# revision0.net
KiCad netlist of a schematic drawn in EAGLE
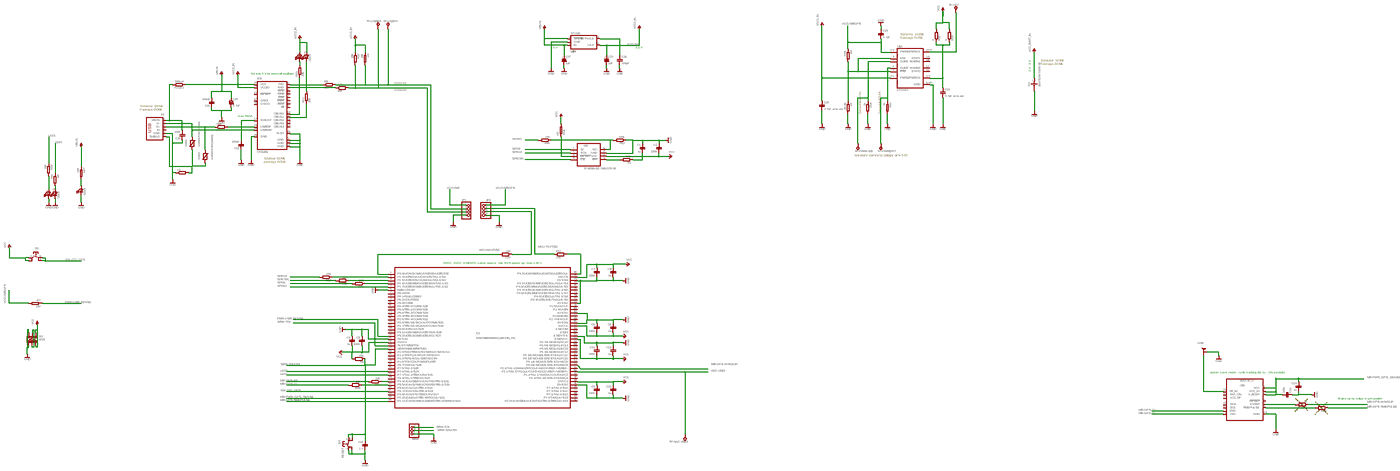
[diagram p0: schematic, sheet 1, overview]
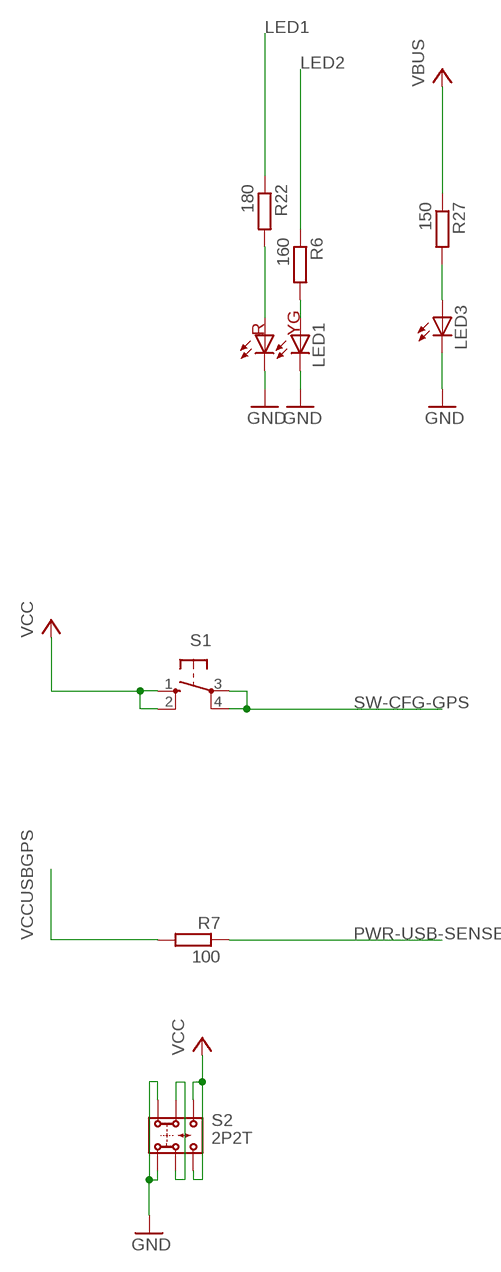
[diagram p1: schematic, sheet 1, part 1 of 4]
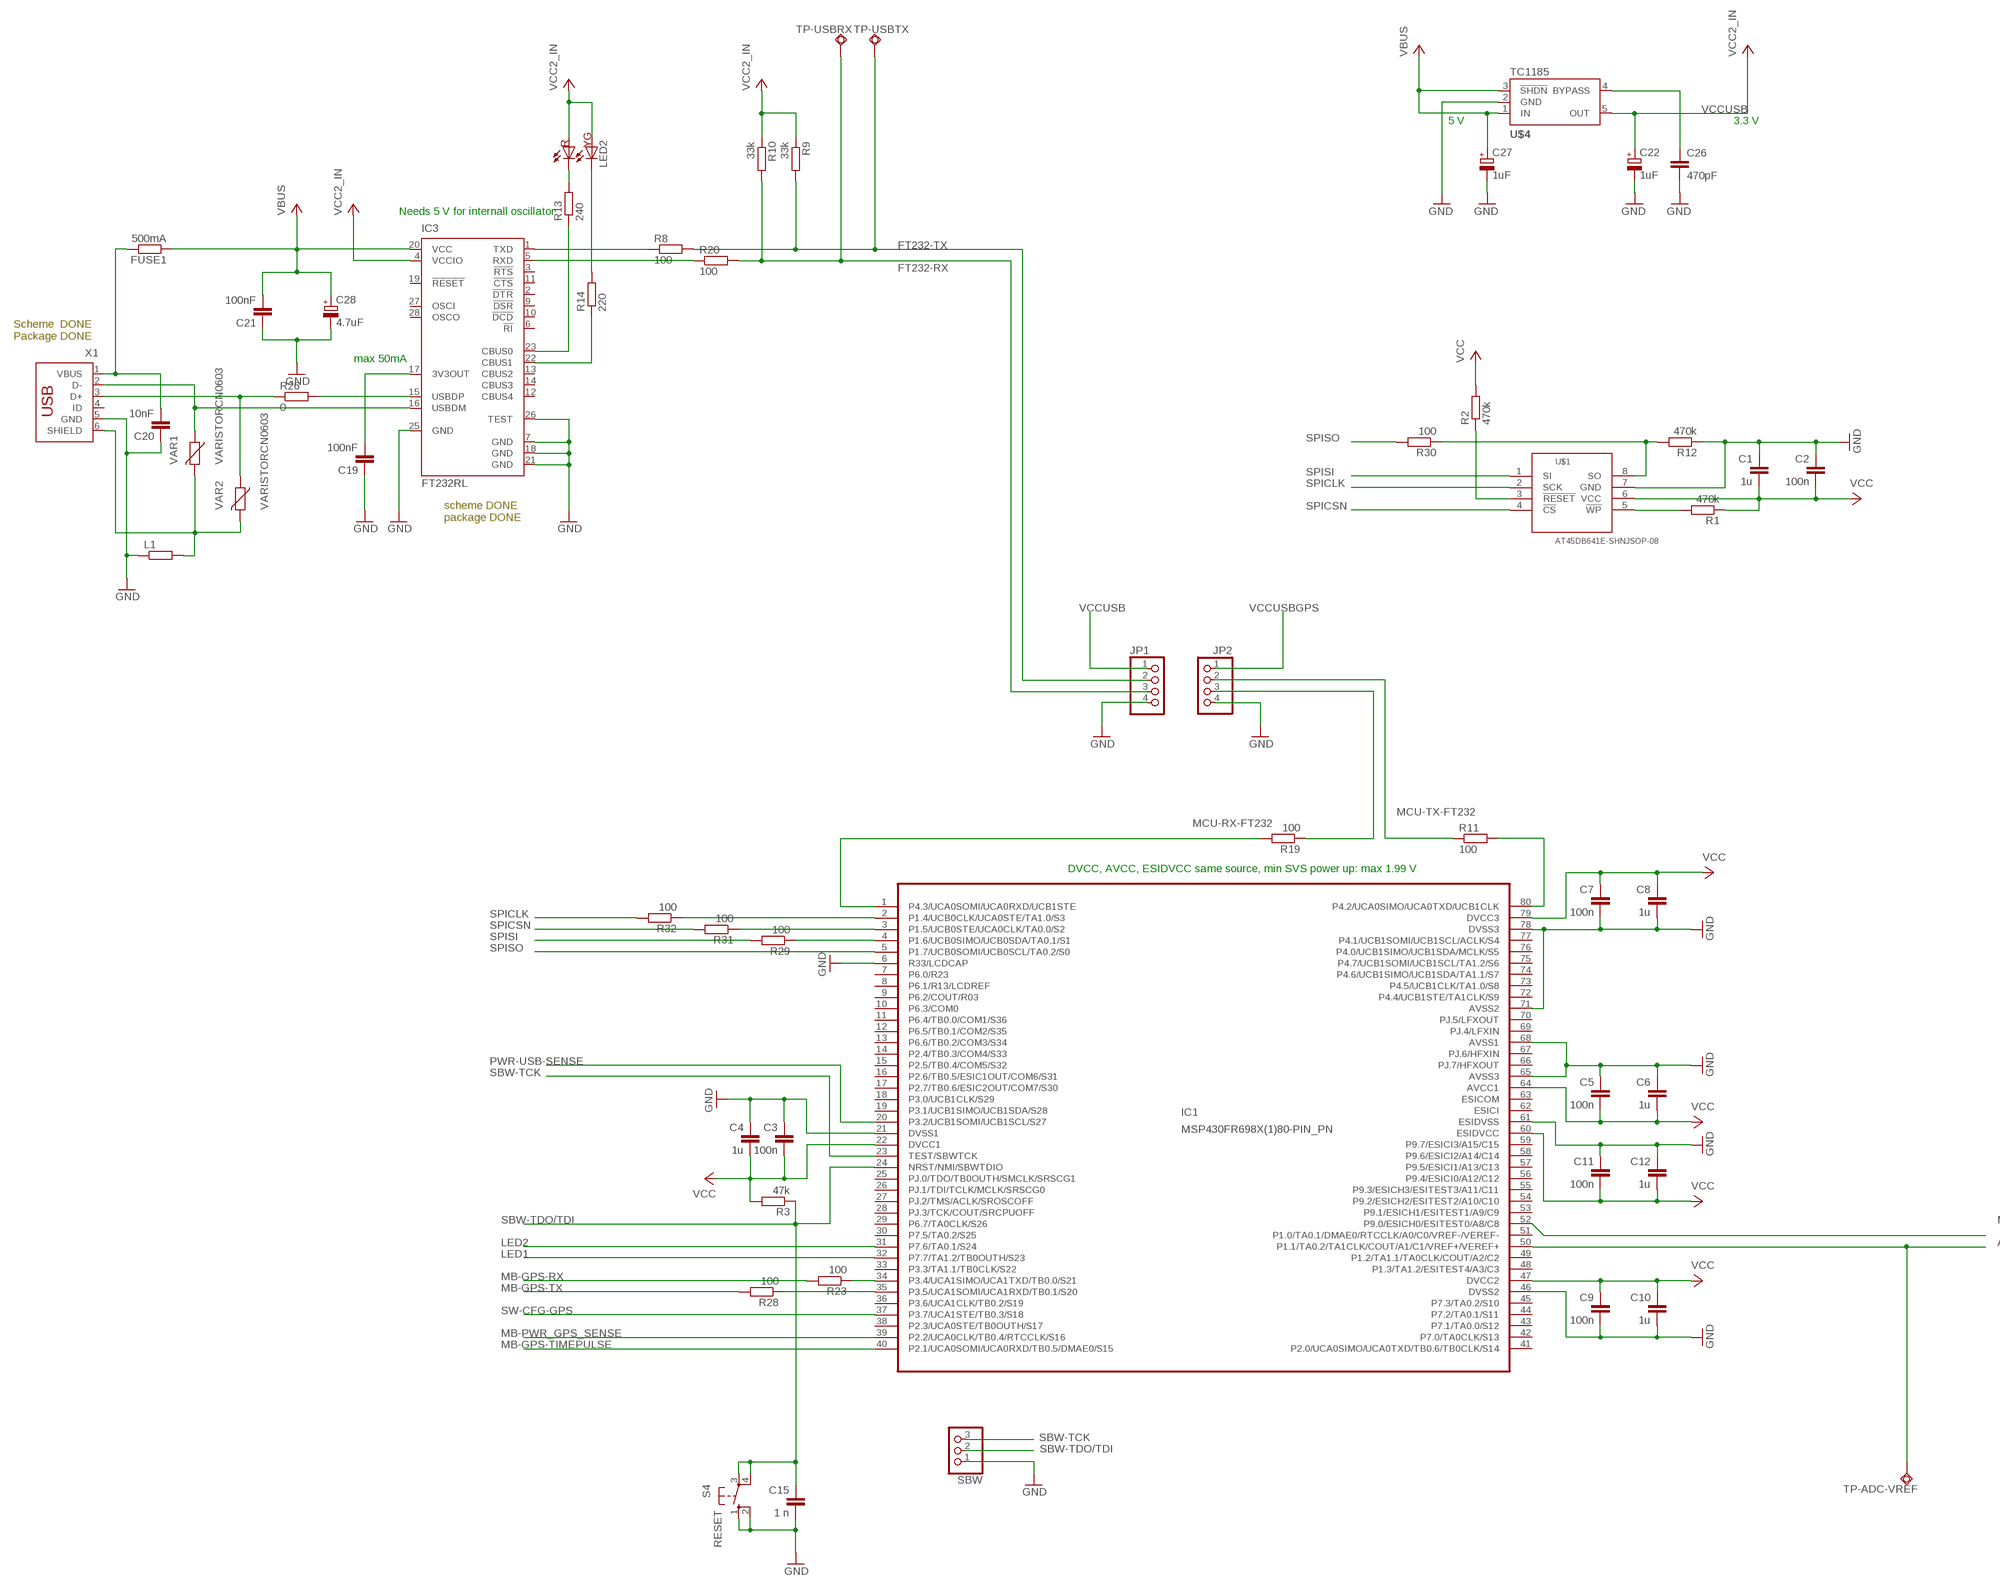
[diagram p2: schematic, sheet 1, part 2 of 4]
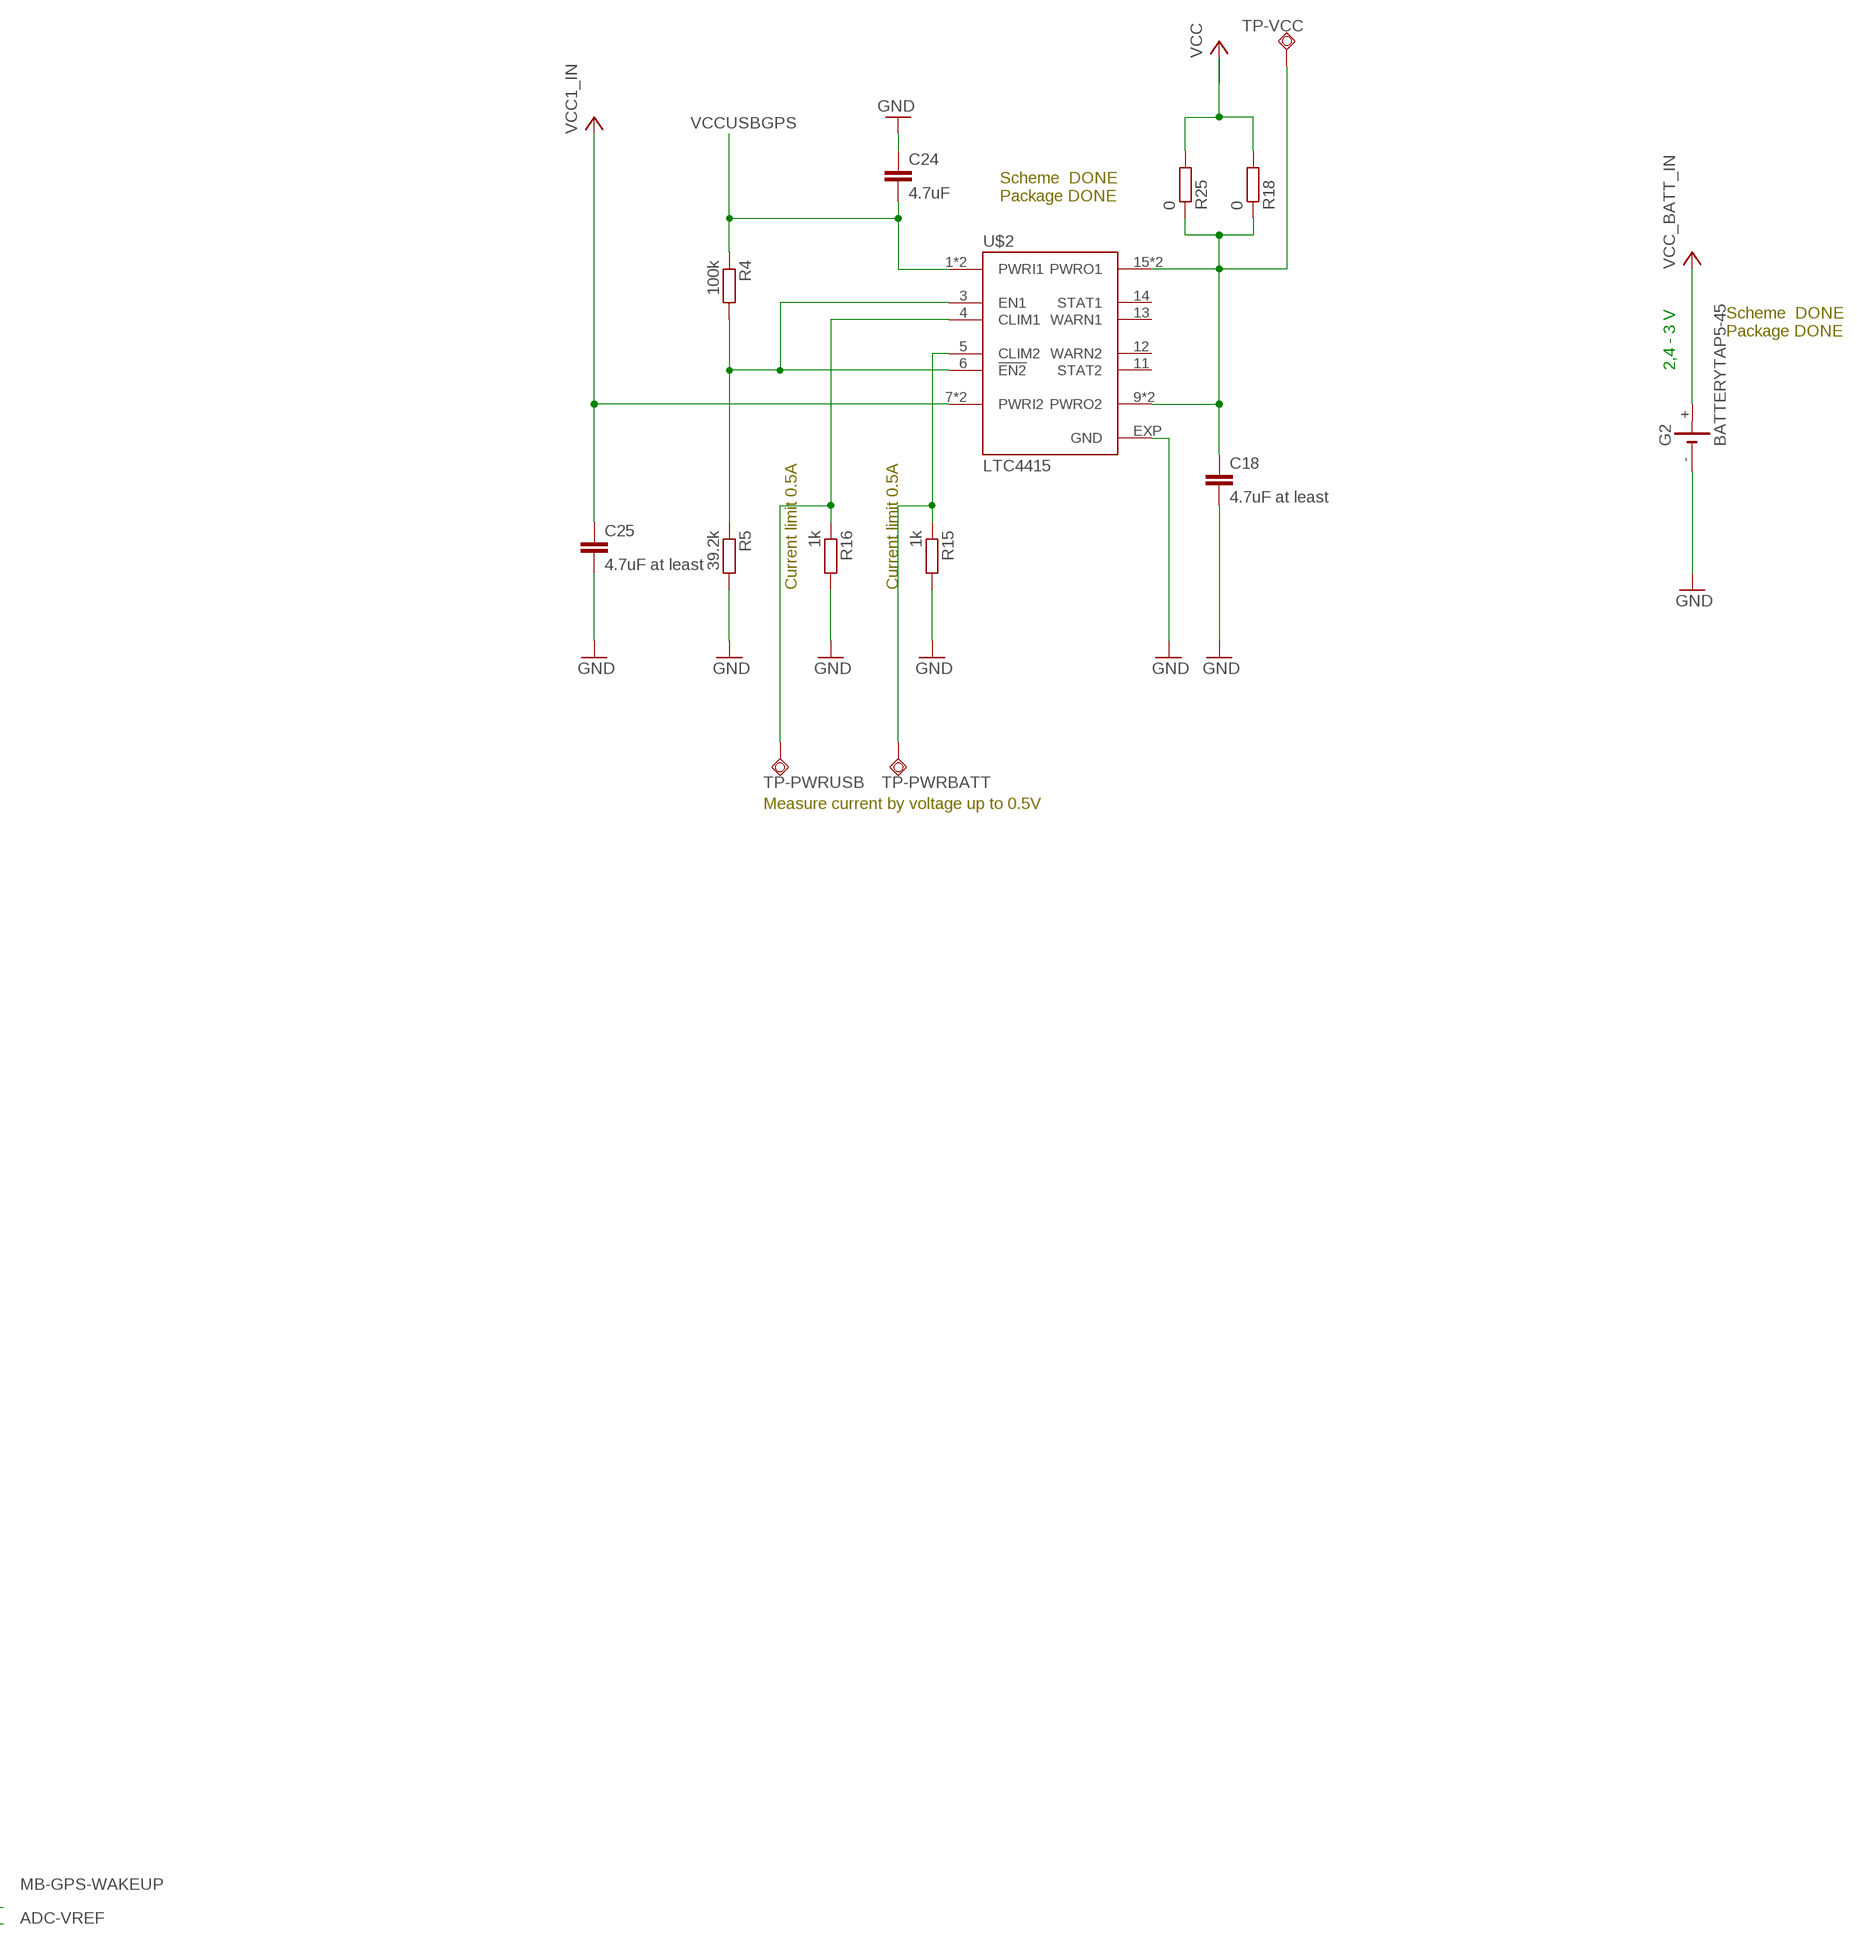
[diagram p3: schematic, sheet 1, part 3 of 4]
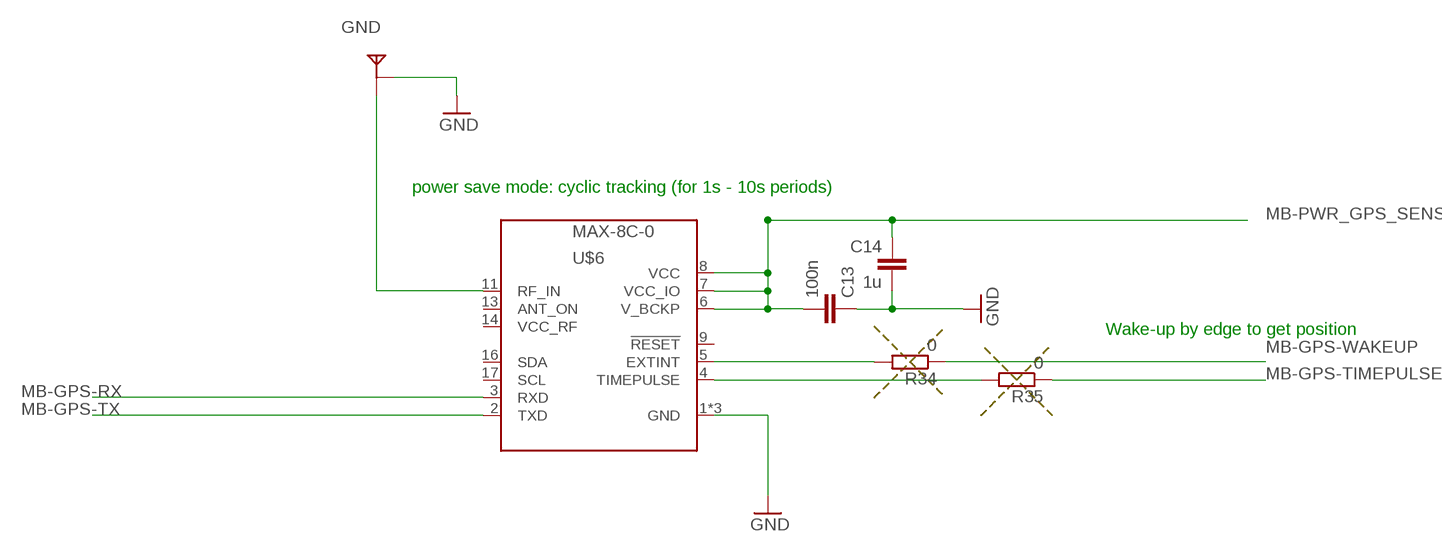
[diagram p4: schematic, sheet 1, part 4 of 4]

(export (version "E")
  (design (tool "Eeschema 10.0.6"))
  (components
    (comp (ref "C1")
      (value "1u")
      (footprint "eagle-import:C0603")
      (libsource (lib "eagle-import") (part "C-EUC0603"))
    )
    (comp (ref "C2")
      (value "100n")
      (footprint "eagle-import:C0603")
      (libsource (lib "eagle-import") (part "C-EUC0603"))
    )
    (comp (ref "C3")
      (value "100n")
      (footprint "eagle-import:C0603")
      (libsource (lib "eagle-import") (part "C-EUC0603"))
    )
    (comp (ref "C4")
      (value "1u")
      (footprint "eagle-import:C0603")
      (libsource (lib "eagle-import") (part "C-EUC0603"))
    )
    (comp (ref "C5")
      (value "100n")
      (footprint "eagle-import:C0603")
      (libsource (lib "eagle-import") (part "C-EUC0603"))
    )
    (comp (ref "C6")
      (value "1u")
      (footprint "eagle-import:C0603")
      (libsource (lib "eagle-import") (part "C-EUC0603"))
    )
    (comp (ref "C7")
      (value "100n")
      (footprint "eagle-import:C0603")
      (libsource (lib "eagle-import") (part "C-EUC0603"))
    )
    (comp (ref "C8")
      (value "1u")
      (footprint "eagle-import:C0603")
      (libsource (lib "eagle-import") (part "C-EUC0603"))
    )
    (comp (ref "C9")
      (value "100n")
      (footprint "eagle-import:C0603")
      (libsource (lib "eagle-import") (part "C-EUC0603"))
    )
    (comp (ref "C10")
      (value "1u")
      (footprint "eagle-import:C0603")
      (libsource (lib "eagle-import") (part "C-EUC0603"))
    )
    (comp (ref "C11")
      (value "100n")
      (footprint "eagle-import:C0603")
      (libsource (lib "eagle-import") (part "C-EUC0603"))
    )
    (comp (ref "C12")
      (value "1u")
      (footprint "eagle-import:C0603")
      (libsource (lib "eagle-import") (part "C-EUC0603"))
    )
    (comp (ref "C13")
      (value "100n")
      (footprint "eagle-import:C0603")
      (libsource (lib "eagle-import") (part "C-EUC0603"))
    )
    (comp (ref "C14")
      (value "1u")
      (footprint "eagle-import:C0603")
      (libsource (lib "eagle-import") (part "C-EUC0603"))
    )
    (comp (ref "C15")
      (value "1 n")
      (footprint "eagle-import:C0603")
      (libsource (lib "eagle-import") (part "C-EUC0603"))
    )
    (comp (ref "C18")
      (value "4.7uF at least")
      (footprint "eagle-import:C0805")
      (libsource (lib "eagle-import") (part "C-EUC0805"))
    )
    (comp (ref "C19")
      (value "100nF")
      (footprint "eagle-import:C0603")
      (libsource (lib "eagle-import") (part "C-EUC0603"))
    )
    (comp (ref "C20")
      (value "10nF")
      (footprint "eagle-import:C0603")
      (libsource (lib "eagle-import") (part "C-EUC0603"))
    )
    (comp (ref "C21")
      (value "100nF")
      (footprint "eagle-import:C0603")
      (libsource (lib "eagle-import") (part "C-EUC0603"))
    )
    (comp (ref "C22")
      (value "1uF")
      (footprint "eagle-import:A_3216-18W")
      (libsource (lib "eagle-import") (part "CPOL-EUA/3216-18W"))
    )
    (comp (ref "C24")
      (value "4.7uF")
      (footprint "eagle-import:C0805")
      (libsource (lib "eagle-import") (part "C-EUC0805"))
    )
    (comp (ref "C25")
      (value "4.7uF at least")
      (footprint "eagle-import:C0805")
      (libsource (lib "eagle-import") (part "C-EUC0805"))
    )
    (comp (ref "C26")
      (value "470pF")
      (footprint "eagle-import:C0603")
      (libsource (lib "eagle-import") (part "C-EUC0603"))
    )
    (comp (ref "C27")
      (value "1uF")
      (footprint "eagle-import:A_3216-18W")
      (libsource (lib "eagle-import") (part "CPOL-EUA/3216-18W"))
    )
    (comp (ref "C28")
      (value "4.7uF")
      (footprint "eagle-import:A_3216-18W")
      (libsource (lib "eagle-import") (part "CPOL-EUA/3216-18W"))
    )
    (comp (ref "FUSE1")
      (value "500mA")
      (footprint "eagle-import:R0805")
      (libsource (lib "eagle-import") (part "R-EU_R0805"))
    )
    (comp (ref "G2")
      (value "BATTERYTAP5-45")
      (footprint "eagle-import:TAP5-45")
      (libsource (lib "eagle-import") (part "BATTERYTAP5-45"))
    )
    (comp (ref "IC1")
      (value "MSP430FR698X(1)80-PIN_PN")
      (footprint "eagle-import:PN_S-PQFP-G80")
      (libsource (lib "eagle-import") (part "MSP430FR698X(1)80-PIN_PN"))
    )
    (comp (ref "IC3")
      (value "FT232RL")
      (footprint "eagle-import:SSOP28")
      (libsource (lib "eagle-import") (part "FT232RL"))
    )
    (comp (ref "JP1")
      (value "PINHD-1X4")
      (footprint "eagle-import:1X04")
      (libsource (lib "eagle-import") (part "PINHD-1X4"))
    )
    (comp (ref "JP2")
      (value "PINHD-1X4")
      (footprint "eagle-import:1X04")
      (libsource (lib "eagle-import") (part "PINHD-1X4"))
    )
    (comp (ref "L1")
      (value "R-EU_R0603")
      (footprint "eagle-import:R0603")
      (libsource (lib "eagle-import") (part "R-EU_R0603"))
    )
    (comp (ref "LED1")
      (value "BILEDBILED")
      (footprint "eagle-import:BILED")
      (libsource (lib "eagle-import") (part "BILEDBILED"))
    )
    (comp (ref "LED2")
      (value "BILEDBILED")
      (footprint "eagle-import:BILED")
      (libsource (lib "eagle-import") (part "BILEDBILED"))
    )
    (comp (ref "LED3")
      (value "LED_E")
      (footprint "eagle-import:LED_KINGBRIGHT0603")
      (libsource (lib "eagle-import") (part "LED_E"))
    )
    (comp (ref "R1")
      (value "470k")
      (footprint "eagle-import:R0603")
      (libsource (lib "eagle-import") (part "R-EU_R0603"))
    )
    (comp (ref "R2")
      (value "470k")
      (footprint "eagle-import:R0603")
      (libsource (lib "eagle-import") (part "R-EU_R0603"))
    )
    (comp (ref "R3")
      (value "47k")
      (footprint "eagle-import:R0603")
      (libsource (lib "eagle-import") (part "R-EU_R0603"))
    )
    (comp (ref "R4")
      (value "100k")
      (footprint "eagle-import:R0603")
      (libsource (lib "eagle-import") (part "R-EU_R0603"))
    )
    (comp (ref "R5")
      (value "39.2k")
      (footprint "eagle-import:R0603")
      (libsource (lib "eagle-import") (part "R-EU_R0603"))
    )
    (comp (ref "R6")
      (value "160")
      (footprint "eagle-import:R0603")
      (libsource (lib "eagle-import") (part "R-EU_R0603"))
    )
    (comp (ref "R7")
      (value "100")
      (footprint "eagle-import:R0603")
      (libsource (lib "eagle-import") (part "R-EU_R0603"))
    )
    (comp (ref "R8")
      (value "100")
      (footprint "eagle-import:R0603")
      (libsource (lib "eagle-import") (part "R-EU_R0603"))
    )
    (comp (ref "R9")
      (value "33k")
      (footprint "eagle-import:R0603")
      (libsource (lib "eagle-import") (part "R-EU_R0603"))
    )
    (comp (ref "R10")
      (value "33k")
      (footprint "eagle-import:R0603")
      (libsource (lib "eagle-import") (part "R-EU_R0603"))
    )
    (comp (ref "R11")
      (value "100")
      (footprint "eagle-import:R0603")
      (libsource (lib "eagle-import") (part "R-EU_R0603"))
    )
    (comp (ref "R12")
      (value "470k")
      (footprint "eagle-import:R0603")
      (libsource (lib "eagle-import") (part "R-EU_R0603"))
    )
    (comp (ref "R13")
      (value "240")
      (footprint "eagle-import:R0603")
      (libsource (lib "eagle-import") (part "R-EU_R0603"))
    )
    (comp (ref "R14")
      (value "220")
      (footprint "eagle-import:R0603")
      (libsource (lib "eagle-import") (part "R-EU_R0603"))
    )
    (comp (ref "R15")
      (value "1k")
      (footprint "eagle-import:R0603")
      (libsource (lib "eagle-import") (part "R-EU_R0603"))
    )
    (comp (ref "R16")
      (value "1k")
      (footprint "eagle-import:R0603")
      (libsource (lib "eagle-import") (part "R-EU_R0603"))
    )
    (comp (ref "R18")
      (value "0")
      (footprint "eagle-import:R0603")
      (libsource (lib "eagle-import") (part "R-EU_R0603"))
    )
    (comp (ref "R19")
      (value "100")
      (footprint "eagle-import:R0603")
      (libsource (lib "eagle-import") (part "R-EU_R0603"))
    )
    (comp (ref "R20")
      (value "100")
      (footprint "eagle-import:R0603")
      (libsource (lib "eagle-import") (part "R-EU_R0603"))
    )
    (comp (ref "R22")
      (value "180")
      (footprint "eagle-import:R0603")
      (libsource (lib "eagle-import") (part "R-EU_R0603"))
    )
    (comp (ref "R23")
      (value "100")
      (footprint "eagle-import:R0603")
      (libsource (lib "eagle-import") (part "R-EU_R0603"))
    )
    (comp (ref "R25")
      (value "0")
      (footprint "eagle-import:R0603")
      (libsource (lib "eagle-import") (part "R-EU_R0603"))
    )
    (comp (ref "R26")
      (value "0")
      (footprint "eagle-import:R0603")
      (libsource (lib "eagle-import") (part "R-EU_R0603"))
    )
    (comp (ref "R27")
      (value "150")
      (footprint "eagle-import:R0603")
      (libsource (lib "eagle-import") (part "R-EU_R0603"))
    )
    (comp (ref "R28")
      (value "100")
      (footprint "eagle-import:R0603")
      (libsource (lib "eagle-import") (part "R-EU_R0603"))
    )
    (comp (ref "R29")
      (value "100")
      (footprint "eagle-import:R0603")
      (libsource (lib "eagle-import") (part "R-EU_R0603"))
    )
    (comp (ref "R30")
      (value "100")
      (footprint "eagle-import:R0603")
      (libsource (lib "eagle-import") (part "R-EU_R0603"))
    )
    (comp (ref "R31")
      (value "100")
      (footprint "eagle-import:R0603")
      (libsource (lib "eagle-import") (part "R-EU_R0603"))
    )
    (comp (ref "R32")
      (value "100")
      (footprint "eagle-import:R0603")
      (libsource (lib "eagle-import") (part "R-EU_R0603"))
    )
    (comp (ref "R34")
      (value "0")
      (footprint "eagle-import:R0603")
      (libsource (lib "eagle-import") (part "R-EU_R0603"))
    )
    (comp (ref "R35")
      (value "0")
      (footprint "eagle-import:R0603")
      (libsource (lib "eagle-import") (part "R-EU_R0603"))
    )
    (comp (ref "S1")
      (value "SWITCH-10-XX")
      (footprint "eagle-import:B3F-10XX")
      (fields (field (name "MPN") "B3F-1000"))
      (libsource (lib "eagle-import") (part "SWITCH-10-XX"))
    )
    (comp (ref "S2")
      (value "2P2T")
      (footprint "eagle-import:2P2T")
      (libsource (lib "eagle-import") (part "2P2T"))
    )
    (comp (ref "S4")
      (value "RESET")
      (footprint "eagle-import:B3F-10XX")
      (fields (field (name "MPN") "B3F-1000"))
      (libsource (lib "eagle-import") (part "SWITCH-10-XX"))
    )
    (comp (ref "SBW")
      (value "PINHD-1X3")
      (footprint "eagle-import:1X03")
      (libsource (lib "eagle-import") (part "PINHD-1X3"))
    )
    (comp (ref "TP-ADC-VREF")
      (value "TPSQTP10R")
      (footprint "eagle-import:TP10R")
      (libsource (lib "eagle-import") (part "TPSQTP10R"))
    )
    (comp (ref "TP-PWRBATT")
      (value "TPSQTP10R")
      (footprint "eagle-import:TP10R")
      (libsource (lib "eagle-import") (part "TPSQTP10R"))
    )
    (comp (ref "TP-PWRUSB")
      (value "TPSQTP10R")
      (footprint "eagle-import:TP10R")
      (libsource (lib "eagle-import") (part "TPSQTP10R"))
    )
    (comp (ref "TP-USBRX")
      (value "TPSQPAD1-13")
      (footprint "eagle-import:P1-13")
      (libsource (lib "eagle-import") (part "TPSQPAD1-13"))
    )
    (comp (ref "TP-USBTX")
      (value "TPSQPAD1-13")
      (footprint "eagle-import:P1-13")
      (libsource (lib "eagle-import") (part "TPSQPAD1-13"))
    )
    (comp (ref "TP-VCC")
      (value "TPSQPAD1-13")
      (footprint "eagle-import:P1-13")
      (libsource (lib "eagle-import") (part "TPSQPAD1-13"))
    )
    (comp (ref "U$1")
      (value "AT45DB641E-SHNJSOP-08")
      (footprint "eagle-import:JSOP-08")
      (libsource (lib "eagle-import") (part "AT45DB641E-SHNJSOP-08"))
    )
    (comp (ref "U$2")
      (value "LTC4415")
      (footprint "eagle-import:MSOP16")
      (libsource (lib "eagle-import") (part "LTC4415"))
    )
    (comp (ref "U$4")
      (value "TC1185")
      (footprint "eagle-import:SOT23-5")
      (libsource (lib "eagle-import") (part "TC1185"))
    )
    (comp (ref "U$5")
      (value "MWSL1251")
      (footprint "eagle-import:MWSL1251")
      (libsource (lib "eagle-import") (part "MWSL1251"))
    )
    (comp (ref "U$6")
      (value "MAX-8C-0")
      (footprint "eagle-import:MAX-8")
      (libsource (lib "eagle-import") (part "MAX-8C-0"))
    )
    (comp (ref "VAR1")
      (value "VARISTORCN0603")
      (footprint "eagle-import:CT_CN0603")
      (libsource (lib "eagle-import") (part "VARISTORCN0603"))
    )
    (comp (ref "VAR2")
      (value "VARISTORCN0603")
      (footprint "eagle-import:CT_CN0603")
      (libsource (lib "eagle-import") (part "VARISTORCN0603"))
    )
    (comp (ref "X1")
      (value "USB-787616")
      (footprint "eagle-import:USB")
      (libsource (lib "eagle-import") (part "USB-787616"))
    )
  )
  (nets
    (net (code "1") (name "/ADC-VREF") (class "Default")
      (node (ref "IC1") (pin "50") (pinfunction "P1.1/TA0.2/TA1CLK/COUT/A1/C1/VREF+/VEREF+_50") (pintype "bidirectional"))
      (node (ref "TP-ADC-VREF") (pin "TP") (pinfunction "TP_TP") (pintype "input"))
    )
    (net (code "2") (name "/FT232-RX") (class "Default")
      (node (ref "JP1") (pin "3") (pinfunction "3_3") (pintype "passive"))
      (node (ref "R10") (pin "2") (pinfunction "2_2") (pintype "passive"))
      (node (ref "R20") (pin "2") (pinfunction "2_2") (pintype "passive"))
      (node (ref "TP-USBRX") (pin "TP") (pinfunction "TP_TP") (pintype "input"))
    )
    (net (code "3") (name "/FT232-TX") (class "Default")
      (node (ref "JP1") (pin "2") (pinfunction "2_2") (pintype "passive"))
      (node (ref "R8") (pin "2") (pinfunction "2_2") (pintype "passive"))
      (node (ref "R9") (pin "2") (pinfunction "2_2") (pintype "passive"))
      (node (ref "TP-USBTX") (pin "TP") (pinfunction "TP_TP") (pintype "input"))
    )
    (net (code "4") (name "/LED1") (class "Default")
      (node (ref "IC1") (pin "32") (pinfunction "P7.7/TA1.2/TB0OUTH/S23_32") (pintype "bidirectional"))
      (node (ref "R22") (pin "1") (pinfunction "1_1") (pintype "passive"))
    )
    (net (code "5") (name "/LED2") (class "Default")
      (node (ref "IC1") (pin "31") (pinfunction "P7.6/TA0.1/S24_31") (pintype "bidirectional"))
      (node (ref "R6") (pin "1") (pinfunction "1_1") (pintype "passive"))
    )
    (net (code "6") (name "/MB-GPS-RX") (class "Default")
      (node (ref "R23") (pin "2") (pinfunction "2_2") (pintype "passive"))
      (node (ref "U$6") (pin "3") (pinfunction "RXD_3") (pintype "input"))
    )
    (net (code "7") (name "/MB-GPS-TIMEPULSE") (class "Default")
      (node (ref "IC1") (pin "40") (pinfunction "P2.1/UCA0SOMI/UCA0RXD/TB0.5/DMAE0/S15_40") (pintype "bidirectional"))
      (node (ref "R35") (pin "1") (pinfunction "1_1") (pintype "passive"))
    )
    (net (code "8") (name "/MB-GPS-TX") (class "Default")
      (node (ref "R28") (pin "2") (pinfunction "2_2") (pintype "passive"))
      (node (ref "U$6") (pin "2") (pinfunction "TXD_2") (pintype "output"))
    )
    (net (code "9") (name "/MB-GPS-WAKEUP") (class "Default")
      (node (ref "IC1") (pin "52") (pinfunction "P9.0/ESICH0/ESITEST0/A8/C8_52") (pintype "bidirectional"))
      (node (ref "R34") (pin "1") (pinfunction "1_1") (pintype "passive"))
    )
    (net (code "10") (name "/MB-PWR_GPS_SENSE") (class "Default")
      (node (ref "C13") (pin "2") (pinfunction "2_2") (pintype "passive"))
      (node (ref "C14") (pin "1") (pinfunction "1_1") (pintype "passive"))
      (node (ref "IC1") (pin "39") (pinfunction "P2.2/UCA0CLK/TB0.4/RTCCLK/S16_39") (pintype "bidirectional"))
      (node (ref "S2") (pin "2.1") (pinfunction "2.1_2.1") (pintype "passive"))
      (node (ref "S2") (pin "2.2") (pinfunction "2.2_2.2") (pintype "passive"))
      (node (ref "U$6") (pin "6") (pinfunction "V_BCKP_6") (pintype "power_in"))
      (node (ref "U$6") (pin "7") (pinfunction "VCC_IO_7") (pintype "power_in"))
      (node (ref "U$6") (pin "8") (pinfunction "VCC_8") (pintype "power_in"))
    )
    (net (code "11") (name "/MCU-RX-FT232") (class "Default")
      (node (ref "IC1") (pin "1") (pinfunction "P4.3/UCA0SOMI/UCA0RXD/UCB1STE_1") (pintype "bidirectional"))
      (node (ref "R19") (pin "2") (pinfunction "2_2") (pintype "passive"))
    )
    (net (code "12") (name "/MCU-TX-FT232") (class "Default")
      (node (ref "JP2") (pin "2") (pinfunction "2_2") (pintype "passive"))
      (node (ref "R11") (pin "1") (pinfunction "1_1") (pintype "passive"))
    )
    (net (code "13") (name "/PWR-USB-SENSE") (class "Default")
      (node (ref "IC1") (pin "20") (pinfunction "P3.2/UCB1SOMI/UCB1SCL/S27_20") (pintype "bidirectional"))
      (node (ref "R7") (pin "1") (pinfunction "1_1") (pintype "passive"))
    )
    (net (code "14") (name "/SBW-TCK") (class "Default")
      (node (ref "IC1") (pin "23") (pinfunction "TEST/SBWTCK_23") (pintype "output"))
      (node (ref "SBW") (pin "3") (pinfunction "3_3") (pintype "passive"))
    )
    (net (code "15") (name "/SBW-TDO{slash}TDI") (class "Default")
      (node (ref "C15") (pin "1") (pinfunction "1_1") (pintype "passive"))
      (node (ref "IC1") (pin "24") (pinfunction "NRST/NMI/SBWTDIO_24") (pintype "bidirectional"))
      (node (ref "R3") (pin "1") (pinfunction "1_1") (pintype "passive"))
      (node (ref "S4") (pin "3") (pinfunction "P_3") (pintype "passive"))
      (node (ref "S4") (pin "4") (pinfunction "P1_4") (pintype "passive"))
      (node (ref "SBW") (pin "2") (pinfunction "2_2") (pintype "passive"))
    )
    (net (code "16") (name "/SPICLK") (class "Default")
      (node (ref "R32") (pin "2") (pinfunction "2_2") (pintype "passive"))
      (node (ref "U$1") (pin "2") (pinfunction "SCK_2") (pintype "input"))
    )
    (net (code "17") (name "/SPICSN") (class "Default")
      (node (ref "R31") (pin "2") (pinfunction "2_2") (pintype "passive"))
      (node (ref "U$1") (pin "4") (pinfunction "~{CS}_4") (pintype "input"))
    )
    (net (code "18") (name "/SPISI") (class "Default")
      (node (ref "R29") (pin "2") (pinfunction "2_2") (pintype "passive"))
      (node (ref "U$1") (pin "1") (pinfunction "SI_1") (pintype "input"))
    )
    (net (code "19") (name "/SPISO") (class "Default")
      (node (ref "IC1") (pin "5") (pinfunction "P1.7/UCB0SOMI/UCB0SCL/TA0.2/S0_5") (pintype "bidirectional"))
      (node (ref "R30") (pin "2") (pinfunction "2_2") (pintype "passive"))
    )
    (net (code "20") (name "/SW-CFG-GPS") (class "Default")
      (node (ref "IC1") (pin "37") (pinfunction "P3.7/UCA1STE/TB0.3/S18_37") (pintype "bidirectional"))
      (node (ref "S1") (pin "3") (pinfunction "P_3") (pintype "passive"))
      (node (ref "S1") (pin "4") (pinfunction "P1_4") (pintype "passive"))
    )
    (net (code "21") (name "/VCCUSBGPS") (class "Default")
      (node (ref "C24") (pin "2") (pinfunction "2_2") (pintype "passive"))
      (node (ref "JP2") (pin "1") (pinfunction "1_1") (pintype "passive"))
      (node (ref "R4") (pin "1") (pinfunction "1_1") (pintype "passive"))
      (node (ref "R7") (pin "2") (pinfunction "2_2") (pintype "passive"))
      (node (ref "U$2") (pin "1") (pinfunction "PWRI1_1") (pintype "power_in"))
      (node (ref "U$2") (pin "2") (pinfunction "PWRI1_2") (pintype "power_in"))
    )
    (net (code "22") (name "GND") (class "Default")
      (node (ref "C1") (pin "1") (pinfunction "1_1") (pintype "passive"))
      (node (ref "C10") (pin "2") (pinfunction "2_2") (pintype "passive"))
      (node (ref "C11") (pin "1") (pinfunction "1_1") (pintype "passive"))
      (node (ref "C12") (pin "1") (pinfunction "1_1") (pintype "passive"))
      (node (ref "C13") (pin "1") (pinfunction "1_1") (pintype "passive"))
      (node (ref "C14") (pin "2") (pinfunction "2_2") (pintype "passive"))
      (node (ref "C15") (pin "2") (pinfunction "2_2") (pintype "passive"))
      (node (ref "C18") (pin "2") (pinfunction "2_2") (pintype "passive"))
      (node (ref "C19") (pin "1") (pinfunction "1_1") (pintype "passive"))
      (node (ref "C2") (pin "1") (pinfunction "1_1") (pintype "passive"))
      (node (ref "C20") (pin "1") (pinfunction "1_1") (pintype "passive"))
      (node (ref "C21") (pin "1") (pinfunction "1_1") (pintype "passive"))
      (node (ref "C22") (pin "-") (pinfunction "-_-") (pintype "passive"))
      (node (ref "C24") (pin "1") (pinfunction "1_1") (pintype "passive"))
      (node (ref "C25") (pin "2") (pinfunction "2_2") (pintype "passive"))
      (node (ref "C26") (pin "2") (pinfunction "2_2") (pintype "passive"))
      (node (ref "C27") (pin "-") (pinfunction "-_-") (pintype "passive"))
      (node (ref "C28") (pin "-") (pinfunction "-_-") (pintype "passive"))
      (node (ref "C3") (pin "1") (pinfunction "1_1") (pintype "passive"))
      (node (ref "C4") (pin "1") (pinfunction "1_1") (pintype "passive"))
      (node (ref "C5") (pin "1") (pinfunction "1_1") (pintype "passive"))
      (node (ref "C6") (pin "1") (pinfunction "1_1") (pintype "passive"))
      (node (ref "C7") (pin "2") (pinfunction "2_2") (pintype "passive"))
      (node (ref "C8") (pin "2") (pinfunction "2_2") (pintype "passive"))
      (node (ref "C9") (pin "2") (pinfunction "2_2") (pintype "passive"))
      (node (ref "G2") (pin "-") (pinfunction "-_-") (pintype "passive"))
      (node (ref "IC1") (pin "21") (pinfunction "DVSS1_21") (pintype "power_in"))
      (node (ref "IC1") (pin "46") (pinfunction "DVSS2_46") (pintype "power_in"))
      (node (ref "IC1") (pin "6") (pinfunction "R33/LCDCAP_6") (pintype "bidirectional"))
      (node (ref "IC1") (pin "61") (pinfunction "ESIDVSS_61") (pintype "power_in"))
      (node (ref "IC1") (pin "65") (pinfunction "AVSS3_65") (pintype "power_in"))
      (node (ref "IC1") (pin "68") (pinfunction "AVSS1_68") (pintype "power_in"))
      (node (ref "IC1") (pin "71") (pinfunction "AVSS2_71") (pintype "power_in"))
      (node (ref "IC1") (pin "78") (pinfunction "DVSS3_78") (pintype "power_in"))
      (node (ref "IC3") (pin "18") (pinfunction "GND_18") (pintype "power_in"))
      (node (ref "IC3") (pin "21") (pinfunction "GND_21") (pintype "power_in"))
      (node (ref "IC3") (pin "25") (pinfunction "GND_25") (pintype "power_in"))
      (node (ref "IC3") (pin "26") (pinfunction "TEST_26") (pintype "input"))
      (node (ref "IC3") (pin "7") (pinfunction "GND_7") (pintype "power_in"))
      (node (ref "JP1") (pin "4") (pinfunction "4_4") (pintype "passive"))
      (node (ref "JP2") (pin "4") (pinfunction "4_4") (pintype "passive"))
      (node (ref "L1") (pin "1") (pinfunction "1_1") (pintype "passive"))
      (node (ref "LED1") (pin "1") (pinfunction "1_1") (pintype "passive"))
      (node (ref "LED1") (pin "3") (pinfunction "3_3") (pintype "passive"))
      (node (ref "LED3") (pin "C") (pinfunction "C_C") (pintype "passive"))
      (node (ref "R12") (pin "1") (pinfunction "1_1") (pintype "passive"))
      (node (ref "R15") (pin "2") (pinfunction "2_2") (pintype "passive"))
      (node (ref "R16") (pin "2") (pinfunction "2_2") (pintype "passive"))
      (node (ref "R5") (pin "2") (pinfunction "2_2") (pintype "passive"))
      (node (ref "S2") (pin "1.1") (pinfunction "1.1_1.1") (pintype "passive"))
      (node (ref "S2") (pin "1.2") (pinfunction "1.2_1.2") (pintype "passive"))
      (node (ref "S4") (pin "1") (pinfunction "S_1") (pintype "passive"))
      (node (ref "S4") (pin "2") (pinfunction "S1_2") (pintype "passive"))
      (node (ref "SBW") (pin "1") (pinfunction "1_1") (pintype "passive"))
      (node (ref "U$1") (pin "7") (pinfunction "GND_7") (pintype "power_in"))
      (node (ref "U$2") (pin "EXP") (pinfunction "GND_EXP") (pintype "power_in"))
      (node (ref "U$4") (pin "2") (pinfunction "GND_2") (pintype "power_in"))
      (node (ref "U$5") (pin "P$1") (pinfunction "GND_P$1") (pintype "power_in"))
      (node (ref "U$5") (pin "P$3") (pinfunction "GND_P$3") (pintype "power_in"))
      (node (ref "U$6") (pin "1") (pinfunction "GND_1") (pintype "power_in"))
      (node (ref "U$6") (pin "10") (pinfunction "GND_10") (pintype "power_in"))
      (node (ref "U$6") (pin "12") (pinfunction "GND_12") (pintype "power_in"))
      (node (ref "X1") (pin "5") (pinfunction "GND_5") (pintype "passive"))
    )
    (net (code "23") (name "Net-(C18-Pad1)") (class "Default")
      (node (ref "C18") (pin "1") (pinfunction "1_1") (pintype "passive"))
      (node (ref "R18") (pin "1") (pinfunction "1_1") (pintype "passive"))
      (node (ref "R25") (pin "1") (pinfunction "1_1") (pintype "passive"))
      (node (ref "TP-VCC") (pin "TP") (pinfunction "TP_TP") (pintype "input"))
      (node (ref "U$2") (pin "10") (pinfunction "PWRO2_10") (pintype "power_in"))
      (node (ref "U$2") (pin "15") (pinfunction "PWRO1_15") (pintype "power_in"))
      (node (ref "U$2") (pin "16") (pinfunction "PWRO1_16") (pintype "power_in"))
      (node (ref "U$2") (pin "9") (pinfunction "PWRO2_9") (pintype "power_in"))
    )
    (net (code "24") (name "Net-(IC1-P1.4{slash}UCB0CLK{slash}UCA0STE{slash}TA1.0{slash}S3)") (class "Default")
      (node (ref "IC1") (pin "2") (pinfunction "P1.4/UCB0CLK/UCA0STE/TA1.0/S3_2") (pintype "bidirectional"))
      (node (ref "R32") (pin "1") (pinfunction "1_1") (pintype "passive"))
    )
    (net (code "25") (name "Net-(IC1-P1.5{slash}UCB0STE{slash}UCA0CLK{slash}TA0.0{slash}S2)") (class "Default")
      (node (ref "IC1") (pin "3") (pinfunction "P1.5/UCB0STE/UCA0CLK/TA0.0/S2_3") (pintype "bidirectional"))
      (node (ref "R31") (pin "1") (pinfunction "1_1") (pintype "passive"))
    )
    (net (code "26") (name "Net-(IC1-P1.6{slash}UCB0SIMO{slash}UCB0SDA{slash}TA0.1{slash}S1)") (class "Default")
      (node (ref "IC1") (pin "4") (pinfunction "P1.6/UCB0SIMO/UCB0SDA/TA0.1/S1_4") (pintype "bidirectional"))
      (node (ref "R29") (pin "1") (pinfunction "1_1") (pintype "passive"))
    )
    (net (code "27") (name "Net-(IC1-P3.4{slash}UCA1SIMO{slash}UCA1TXD{slash}TB0.0{slash}S21)") (class "Default")
      (node (ref "IC1") (pin "34") (pinfunction "P3.4/UCA1SIMO/UCA1TXD/TB0.0/S21_34") (pintype "bidirectional"))
      (node (ref "R23") (pin "1") (pinfunction "1_1") (pintype "passive"))
    )
    (net (code "28") (name "Net-(IC1-P3.5{slash}UCA1SOMI{slash}UCA1RXD{slash}TB0.1{slash}S20)") (class "Default")
      (node (ref "IC1") (pin "35") (pinfunction "P3.5/UCA1SOMI/UCA1RXD/TB0.1/S20_35") (pintype "bidirectional"))
      (node (ref "R28") (pin "1") (pinfunction "1_1") (pintype "passive"))
    )
    (net (code "29") (name "Net-(IC1-P4.2{slash}UCA0SIMO{slash}UCA0TXD{slash}UCB1CLK)") (class "Default")
      (node (ref "IC1") (pin "80") (pinfunction "P4.2/UCA0SIMO/UCA0TXD/UCB1CLK_80") (pintype "bidirectional"))
      (node (ref "R11") (pin "2") (pinfunction "2_2") (pintype "passive"))
    )
    (net (code "30") (name "Net-(IC3-3V3OUT)") (class "Default")
      (node (ref "C19") (pin "2") (pinfunction "2_2") (pintype "passive"))
      (node (ref "IC3") (pin "17") (pinfunction "3V3OUT_17") (pintype "output"))
    )
    (net (code "31") (name "Net-(IC3-CBUS0)") (class "Default")
      (node (ref "IC3") (pin "23") (pinfunction "CBUS0_23") (pintype "bidirectional"))
      (node (ref "R13") (pin "1") (pinfunction "1_1") (pintype "passive"))
    )
    (net (code "32") (name "Net-(IC3-CBUS1)") (class "Default")
      (node (ref "IC3") (pin "22") (pinfunction "CBUS1_22") (pintype "bidirectional"))
      (node (ref "R14") (pin "1") (pinfunction "1_1") (pintype "passive"))
    )
    (net (code "33") (name "Net-(IC3-RXD)") (class "Default")
      (node (ref "IC3") (pin "5") (pinfunction "RXD_5") (pintype "input"))
      (node (ref "R20") (pin "1") (pinfunction "1_1") (pintype "passive"))
    )
    (net (code "34") (name "Net-(IC3-TXD)") (class "Default")
      (node (ref "IC3") (pin "1") (pinfunction "TXD_1") (pintype "output"))
      (node (ref "R8") (pin "1") (pinfunction "1_1") (pintype "passive"))
    )
    (net (code "35") (name "Net-(IC3-USBDM)") (class "Default")
      (node (ref "IC3") (pin "16") (pinfunction "USBDM_16") (pintype "bidirectional"))
      (node (ref "VAR1") (pin "1") (pinfunction "1_1") (pintype "passive"))
      (node (ref "X1") (pin "2") (pinfunction "D-_2") (pintype "passive"))
    )
    (net (code "36") (name "Net-(IC3-USBDP)") (class "Default")
      (node (ref "IC3") (pin "15") (pinfunction "USBDP_15") (pintype "bidirectional"))
      (node (ref "R26") (pin "2") (pinfunction "2_2") (pintype "passive"))
    )
    (net (code "37") (name "Net-(JP2-Pad3)") (class "Default")
      (node (ref "JP2") (pin "3") (pinfunction "3_3") (pintype "passive"))
      (node (ref "R19") (pin "1") (pinfunction "1_1") (pintype "passive"))
    )
    (net (code "38") (name "Net-(LED1-Pad2)") (class "Default")
      (node (ref "LED1") (pin "2") (pinfunction "2_2") (pintype "passive"))
      (node (ref "R22") (pin "2") (pinfunction "2_2") (pintype "passive"))
    )
    (net (code "39") (name "Net-(LED1-Pad4)") (class "Default")
      (node (ref "LED1") (pin "4") (pinfunction "4_4") (pintype "passive"))
      (node (ref "R6") (pin "2") (pinfunction "2_2") (pintype "passive"))
    )
    (net (code "40") (name "Net-(LED2-Pad1)") (class "Default")
      (node (ref "LED2") (pin "1") (pinfunction "1_1") (pintype "passive"))
      (node (ref "R13") (pin "2") (pinfunction "2_2") (pintype "passive"))
    )
    (net (code "41") (name "Net-(LED2-Pad3)") (class "Default")
      (node (ref "LED2") (pin "3") (pinfunction "3_3") (pintype "passive"))
      (node (ref "R14") (pin "2") (pinfunction "2_2") (pintype "passive"))
    )
    (net (code "42") (name "Net-(LED3-PadA)") (class "Default")
      (node (ref "LED3") (pin "A") (pinfunction "A_A") (pintype "passive"))
      (node (ref "R27") (pin "2") (pinfunction "2_2") (pintype "passive"))
    )
    (net (code "43") (name "Net-(U$1-SO)") (class "Default")
      (node (ref "R12") (pin "2") (pinfunction "2_2") (pintype "passive"))
      (node (ref "R30") (pin "1") (pinfunction "1_1") (pintype "passive"))
      (node (ref "U$1") (pin "8") (pinfunction "SO_8") (pintype "output"))
    )
    (net (code "44") (name "Net-(U$1-~{RESET})") (class "Default")
      (node (ref "R2") (pin "1") (pinfunction "1_1") (pintype "passive"))
      (node (ref "U$1") (pin "3") (pinfunction "~{RESET}_3") (pintype "input"))
    )
    (net (code "45") (name "Net-(U$1-~{WP})") (class "Default")
      (node (ref "R1") (pin "2") (pinfunction "2_2") (pintype "passive"))
      (node (ref "U$1") (pin "5") (pinfunction "~{WP}_5") (pintype "input"))
    )
    (net (code "46") (name "Net-(U$2-CLIM1)") (class "Default")
      (node (ref "R16") (pin "1") (pinfunction "1_1") (pintype "passive"))
      (node (ref "TP-PWRUSB") (pin "TP") (pinfunction "TP_TP") (pintype "input"))
      (node (ref "U$2") (pin "4") (pinfunction "CLIM1_4") (pintype "bidirectional"))
    )
    (net (code "47") (name "Net-(U$2-CLIM2)") (class "Default")
      (node (ref "R15") (pin "1") (pinfunction "1_1") (pintype "passive"))
      (node (ref "TP-PWRBATT") (pin "TP") (pinfunction "TP_TP") (pintype "input"))
      (node (ref "U$2") (pin "5") (pinfunction "CLIM2_5") (pintype "bidirectional"))
    )
    (net (code "48") (name "Net-(U$2-EN1)") (class "Default")
      (node (ref "R4") (pin "2") (pinfunction "2_2") (pintype "passive"))
      (node (ref "R5") (pin "1") (pinfunction "1_1") (pintype "passive"))
      (node (ref "U$2") (pin "3") (pinfunction "EN1_3") (pintype "input"))
      (node (ref "U$2") (pin "6") (pinfunction "~{EN2}_6") (pintype "input"))
    )
    (net (code "49") (name "Net-(U$4-BYPASS)") (class "Default")
      (node (ref "C26") (pin "1") (pinfunction "1_1") (pintype "passive"))
      (node (ref "U$4") (pin "4") (pinfunction "BYPASS_4") (pintype "passive"))
    )
    (net (code "50") (name "Net-(U$5-FEED)") (class "Default")
      (node (ref "U$5") (pin "P$2") (pinfunction "FEED_P$2") (pintype "bidirectional"))
      (node (ref "U$6") (pin "11") (pinfunction "RF_IN_11") (pintype "input"))
    )
    (net (code "51") (name "Net-(U$6-EXTINT)") (class "Default")
      (node (ref "R34") (pin "2") (pinfunction "2_2") (pintype "passive"))
      (node (ref "U$6") (pin "5") (pinfunction "EXTINT_5") (pintype "input"))
    )
    (net (code "52") (name "Net-(U$6-TIMEPULSE)") (class "Default")
      (node (ref "R35") (pin "2") (pinfunction "2_2") (pintype "passive"))
      (node (ref "U$6") (pin "4") (pinfunction "TIMEPULSE_4") (pintype "output"))
    )
    (net (code "53") (name "Net-(X1-D+)") (class "Default")
      (node (ref "R26") (pin "1") (pinfunction "1_1") (pintype "passive"))
      (node (ref "VAR2") (pin "1") (pinfunction "1_1") (pintype "passive"))
      (node (ref "X1") (pin "3") (pinfunction "D+_3") (pintype "passive"))
    )
    (net (code "54") (name "Net-(X1-SHIELD)") (class "Default")
      (node (ref "L1") (pin "2") (pinfunction "2_2") (pintype "passive"))
      (node (ref "VAR1") (pin "2") (pinfunction "2_2") (pintype "passive"))
      (node (ref "VAR2") (pin "2") (pinfunction "2_2") (pintype "passive"))
      (node (ref "X1") (pin "6") (pinfunction "SHIELD_6") (pintype "passive"))
    )
    (net (code "55") (name "Net-(X1-VBUS)") (class "Default")
      (node (ref "C20") (pin "2") (pinfunction "2_2") (pintype "passive"))
      (node (ref "FUSE1") (pin "2") (pinfunction "2_2") (pintype "passive"))
      (node (ref "X1") (pin "1") (pinfunction "VBUS_1") (pintype "passive"))
    )
    (net (code "56") (name "VBUS") (class "Default")
      (node (ref "C21") (pin "2") (pinfunction "2_2") (pintype "passive"))
      (node (ref "C27") (pin "+") (pinfunction "+_+") (pintype "passive"))
      (node (ref "C28") (pin "+") (pinfunction "+_+") (pintype "passive"))
      (node (ref "FUSE1") (pin "1") (pinfunction "1_1") (pintype "passive"))
      (node (ref "IC3") (pin "20") (pinfunction "VCC_20") (pintype "power_in"))
      (node (ref "R27") (pin "1") (pinfunction "1_1") (pintype "passive"))
      (node (ref "U$4") (pin "1") (pinfunction "IN_1") (pintype "power_in"))
      (node (ref "U$4") (pin "3") (pinfunction "~{SHDN}_3") (pintype "input"))
    )
    (net (code "57") (name "VCC") (class "Default")
      (node (ref "C1") (pin "2") (pinfunction "2_2") (pintype "passive"))
      (node (ref "C10") (pin "1") (pinfunction "1_1") (pintype "passive"))
      (node (ref "C11") (pin "2") (pinfunction "2_2") (pintype "passive"))
      (node (ref "C12") (pin "2") (pinfunction "2_2") (pintype "passive"))
      (node (ref "C2") (pin "2") (pinfunction "2_2") (pintype "passive"))
      (node (ref "C3") (pin "2") (pinfunction "2_2") (pintype "passive"))
      (node (ref "C4") (pin "2") (pinfunction "2_2") (pintype "passive"))
      (node (ref "C5") (pin "2") (pinfunction "2_2") (pintype "passive"))
      (node (ref "C6") (pin "2") (pinfunction "2_2") (pintype "passive"))
      (node (ref "C7") (pin "1") (pinfunction "1_1") (pintype "passive"))
      (node (ref "C8") (pin "1") (pinfunction "1_1") (pintype "passive"))
      (node (ref "C9") (pin "1") (pinfunction "1_1") (pintype "passive"))
      (node (ref "IC1") (pin "22") (pinfunction "DVCC1_22") (pintype "power_in"))
      (node (ref "IC1") (pin "47") (pinfunction "DVCC2_47") (pintype "power_in"))
      (node (ref "IC1") (pin "60") (pinfunction "ESIDVCC_60") (pintype "power_in"))
      (node (ref "IC1") (pin "64") (pinfunction "AVCC1_64") (pintype "power_in"))
      (node (ref "IC1") (pin "79") (pinfunction "DVCC3_79") (pintype "power_in"))
      (node (ref "R1") (pin "1") (pinfunction "1_1") (pintype "passive"))
      (node (ref "R18") (pin "2") (pinfunction "2_2") (pintype "passive"))
      (node (ref "R2") (pin "2") (pinfunction "2_2") (pintype "passive"))
      (node (ref "R25") (pin "2") (pinfunction "2_2") (pintype "passive"))
      (node (ref "R3") (pin "2") (pinfunction "2_2") (pintype "passive"))
      (node (ref "S1") (pin "1") (pinfunction "S_1") (pintype "passive"))
      (node (ref "S1") (pin "2") (pinfunction "S1_2") (pintype "passive"))
      (node (ref "S2") (pin "3.1") (pinfunction "3.1_3.1") (pintype "passive"))
      (node (ref "S2") (pin "3.2") (pinfunction "3.2_3.2") (pintype "passive"))
      (node (ref "U$1") (pin "6") (pinfunction "VCC_6") (pintype "power_in"))
    )
    (net (code "58") (name "VCC1_IN") (class "Default")
      (node (ref "C25") (pin "1") (pinfunction "1_1") (pintype "passive"))
      (node (ref "G2") (pin "+") (pinfunction "+_+") (pintype "passive"))
      (node (ref "U$2") (pin "7") (pinfunction "PWRI2_7") (pintype "power_in"))
      (node (ref "U$2") (pin "8") (pinfunction "PWRI2_8") (pintype "power_in"))
    )
    (net (code "59") (name "VCC2_IN") (class "Default")
      (node (ref "C22") (pin "+") (pinfunction "+_+") (pintype "passive"))
      (node (ref "IC3") (pin "4") (pinfunction "VCCIO_4") (pintype "power_in"))
      (node (ref "JP1") (pin "1") (pinfunction "1_1") (pintype "passive"))
      (node (ref "LED2") (pin "2") (pinfunction "2_2") (pintype "passive"))
      (node (ref "LED2") (pin "4") (pinfunction "4_4") (pintype "passive"))
      (node (ref "R10") (pin "1") (pinfunction "1_1") (pintype "passive"))
      (node (ref "R9") (pin "1") (pinfunction "1_1") (pintype "passive"))
      (node (ref "U$4") (pin "5") (pinfunction "OUT_5") (pintype "power_in"))
    )
    (net (code "60") (name "unconnected-(IC1-ESICI-Pad62)") (class "Default")
      (node (ref "IC1") (pin "62") (pinfunction "ESICI_62") (pintype "bidirectional"))
    )
    (net (code "61") (name "unconnected-(IC1-ESICOM-Pad63)") (class "Default")
      (node (ref "IC1") (pin "63") (pinfunction "ESICOM_63") (pintype "bidirectional"))
    )
    (net (code "62") (name "unconnected-(IC1-P1.0{slash}TA0.1{slash}DMAE0{slash}RTCCLK{slash}A0{slash}C0{slash}VREF-{slash}VEREF--Pad51)") (class "Default")
      (node (ref "IC1") (pin "51") (pinfunction "P1.0/TA0.1/DMAE0/RTCCLK/A0/C0/VREF-/VEREF-_51") (pintype "bidirectional"))
    )
    (net (code "63") (name "unconnected-(IC1-P1.2{slash}TA1.1{slash}TA0CLK{slash}COUT{slash}A2{slash}C2-Pad49)") (class "Default")
      (node (ref "IC1") (pin "49") (pinfunction "P1.2/TA1.1/TA0CLK/COUT/A2/C2_49") (pintype "bidirectional"))
    )
    (net (code "64") (name "unconnected-(IC1-P1.3{slash}TA1.2{slash}ESITEST4{slash}A3{slash}C3-Pad48)") (class "Default")
      (node (ref "IC1") (pin "48") (pinfunction "P1.3/TA1.2/ESITEST4/A3/C3_48") (pintype "bidirectional"))
    )
    (net (code "65") (name "unconnected-(IC1-P2.0{slash}UCA0SIMO{slash}UCA0TXD{slash}TB0.6{slash}TB0CLK{slash}S14-Pad41)") (class "Default")
      (node (ref "IC1") (pin "41") (pinfunction "P2.0/UCA0SIMO/UCA0TXD/TB0.6/TB0CLK/S14_41") (pintype "bidirectional"))
    )
    (net (code "66") (name "unconnected-(IC1-P2.3{slash}UCA0STE{slash}TB0OUTH{slash}S17-Pad38)") (class "Default")
      (node (ref "IC1") (pin "38") (pinfunction "P2.3/UCA0STE/TB0OUTH/S17_38") (pintype "bidirectional"))
    )
    (net (code "67") (name "unconnected-(IC1-P2.4{slash}TB0.3{slash}COM4{slash}S33-Pad14)") (class "Default")
      (node (ref "IC1") (pin "14") (pinfunction "P2.4/TB0.3/COM4/S33_14") (pintype "bidirectional"))
    )
    (net (code "68") (name "unconnected-(IC1-P2.5{slash}TB0.4{slash}COM5{slash}S32-Pad15)") (class "Default")
      (node (ref "IC1") (pin "15") (pinfunction "P2.5/TB0.4/COM5/S32_15") (pintype "bidirectional"))
    )
    (net (code "69") (name "unconnected-(IC1-P2.6{slash}TB0.5{slash}ESIC1OUT{slash}COM6{slash}S31-Pad16)") (class "Default")
      (node (ref "IC1") (pin "16") (pinfunction "P2.6/TB0.5/ESIC1OUT/COM6/S31_16") (pintype "bidirectional"))
    )
    (net (code "70") (name "unconnected-(IC1-P2.7{slash}TB0.6{slash}ESIC2OUT{slash}COM7{slash}S30-Pad17)") (class "Default")
      (node (ref "IC1") (pin "17") (pinfunction "P2.7/TB0.6/ESIC2OUT/COM7/S30_17") (pintype "bidirectional"))
    )
    (net (code "71") (name "unconnected-(IC1-P3.0{slash}UCB1CLK{slash}S29-Pad18)") (class "Default")
      (node (ref "IC1") (pin "18") (pinfunction "P3.0/UCB1CLK/S29_18") (pintype "bidirectional"))
    )
    (net (code "72") (name "unconnected-(IC1-P3.1{slash}UCB1SIMO{slash}UCB1SDA{slash}S28-Pad19)") (class "Default")
      (node (ref "IC1") (pin "19") (pinfunction "P3.1/UCB1SIMO/UCB1SDA/S28_19") (pintype "bidirectional"))
    )
    (net (code "73") (name "unconnected-(IC1-P3.3{slash}TA1.1{slash}TB0CLK{slash}S22-Pad33)") (class "Default")
      (node (ref "IC1") (pin "33") (pinfunction "P3.3/TA1.1/TB0CLK/S22_33") (pintype "bidirectional"))
    )
    (net (code "74") (name "unconnected-(IC1-P3.6{slash}UCA1CLK{slash}TB0.2{slash}S19-Pad36)") (class "Default")
      (node (ref "IC1") (pin "36") (pinfunction "P3.6/UCA1CLK/TB0.2/S19_36") (pintype "bidirectional"))
    )
    (net (code "75") (name "unconnected-(IC1-P4.0{slash}UCB1SIMO{slash}UCB1SDA{slash}MCLK{slash}S5-Pad76)") (class "Default")
      (node (ref "IC1") (pin "76") (pinfunction "P4.0/UCB1SIMO/UCB1SDA/MCLK/S5_76") (pintype "bidirectional"))
    )
    (net (code "76") (name "unconnected-(IC1-P4.1{slash}UCB1SOMI{slash}UCB1SCL{slash}ACLK{slash}S4-Pad77)") (class "Default")
      (node (ref "IC1") (pin "77") (pinfunction "P4.1/UCB1SOMI/UCB1SCL/ACLK/S4_77") (pintype "bidirectional"))
    )
    (net (code "77") (name "unconnected-(IC1-P4.4{slash}UCB1STE{slash}TA1CLK{slash}S9-Pad72)") (class "Default")
      (node (ref "IC1") (pin "72") (pinfunction "P4.4/UCB1STE/TA1CLK/S9_72") (pintype "bidirectional"))
    )
    (net (code "78") (name "unconnected-(IC1-P4.5{slash}UCB1CLK{slash}TA1.0{slash}S8-Pad73)") (class "Default")
      (node (ref "IC1") (pin "73") (pinfunction "P4.5/UCB1CLK/TA1.0/S8_73") (pintype "bidirectional"))
    )
    (net (code "79") (name "unconnected-(IC1-P4.6{slash}UCB1SIMO{slash}UCB1SDA{slash}TA1.1{slash}S7-Pad74)") (class "Default")
      (node (ref "IC1") (pin "74") (pinfunction "P4.6/UCB1SIMO/UCB1SDA/TA1.1/S7_74") (pintype "bidirectional"))
    )
    (net (code "80") (name "unconnected-(IC1-P4.7{slash}UCB1SOMI{slash}UCB1SCL{slash}TA1.2{slash}S6-Pad75)") (class "Default")
      (node (ref "IC1") (pin "75") (pinfunction "P4.7/UCB1SOMI/UCB1SCL/TA1.2/S6_75") (pintype "bidirectional"))
    )
    (net (code "81") (name "unconnected-(IC1-P6.0{slash}R23-Pad7)") (class "Default")
      (node (ref "IC1") (pin "7") (pinfunction "P6.0/R23_7") (pintype "bidirectional"))
    )
    (net (code "82") (name "unconnected-(IC1-P6.1{slash}R13{slash}LCDREF-Pad8)") (class "Default")
      (node (ref "IC1") (pin "8") (pinfunction "P6.1/R13/LCDREF_8") (pintype "bidirectional"))
    )
    (net (code "83") (name "unconnected-(IC1-P6.2{slash}COUT{slash}R03-Pad9)") (class "Default")
      (node (ref "IC1") (pin "9") (pinfunction "P6.2/COUT/R03_9") (pintype "bidirectional"))
    )
    (net (code "84") (name "unconnected-(IC1-P6.3{slash}COM0-Pad10)") (class "Default")
      (node (ref "IC1") (pin "10") (pinfunction "P6.3/COM0_10") (pintype "bidirectional"))
    )
    (net (code "85") (name "unconnected-(IC1-P6.4{slash}TB0.0{slash}COM1{slash}S36-Pad11)") (class "Default")
      (node (ref "IC1") (pin "11") (pinfunction "P6.4/TB0.0/COM1/S36_11") (pintype "bidirectional"))
    )
    (net (code "86") (name "unconnected-(IC1-P6.5{slash}TB0.1{slash}COM2{slash}S35-Pad12)") (class "Default")
      (node (ref "IC1") (pin "12") (pinfunction "P6.5/TB0.1/COM2/S35_12") (pintype "bidirectional"))
    )
    (net (code "87") (name "unconnected-(IC1-P6.6{slash}TB0.2{slash}COM3{slash}S34-Pad13)") (class "Default")
      (node (ref "IC1") (pin "13") (pinfunction "P6.6/TB0.2/COM3/S34_13") (pintype "bidirectional"))
    )
    (net (code "88") (name "unconnected-(IC1-P6.7{slash}TA0CLK{slash}S26-Pad29)") (class "Default")
      (node (ref "IC1") (pin "29") (pinfunction "P6.7/TA0CLK/S26_29") (pintype "bidirectional"))
    )
    (net (code "89") (name "unconnected-(IC1-P7.0{slash}TA0CLK{slash}S13-Pad42)") (class "Default")
      (node (ref "IC1") (pin "42") (pinfunction "P7.0/TA0CLK/S13_42") (pintype "bidirectional"))
    )
    (net (code "90") (name "unconnected-(IC1-P7.1{slash}TA0.0{slash}S12-Pad43)") (class "Default")
      (node (ref "IC1") (pin "43") (pinfunction "P7.1/TA0.0/S12_43") (pintype "bidirectional"))
    )
    (net (code "91") (name "unconnected-(IC1-P7.2{slash}TA0.1{slash}S11-Pad44)") (class "Default")
      (node (ref "IC1") (pin "44") (pinfunction "P7.2/TA0.1/S11_44") (pintype "bidirectional"))
    )
    (net (code "92") (name "unconnected-(IC1-P7.3{slash}TA0.2{slash}S10-Pad45)") (class "Default")
      (node (ref "IC1") (pin "45") (pinfunction "P7.3/TA0.2/S10_45") (pintype "bidirectional"))
    )
    (net (code "93") (name "unconnected-(IC1-P7.5{slash}TA0.2{slash}S25-Pad30)") (class "Default")
      (node (ref "IC1") (pin "30") (pinfunction "P7.5/TA0.2/S25_30") (pintype "bidirectional"))
    )
    (net (code "94") (name "unconnected-(IC1-P9.1{slash}ESICH1{slash}ESITEST1{slash}A9{slash}C9-Pad53)") (class "Default")
      (node (ref "IC1") (pin "53") (pinfunction "P9.1/ESICH1/ESITEST1/A9/C9_53") (pintype "bidirectional"))
    )
    (net (code "95") (name "unconnected-(IC1-P9.2{slash}ESICH2{slash}ESITEST2{slash}A10{slash}C10-Pad54)") (class "Default")
      (node (ref "IC1") (pin "54") (pinfunction "P9.2/ESICH2/ESITEST2/A10/C10_54") (pintype "bidirectional"))
    )
    (net (code "96") (name "unconnected-(IC1-P9.3{slash}ESICH3{slash}ESITEST3{slash}A11{slash}C11-Pad55)") (class "Default")
      (node (ref "IC1") (pin "55") (pinfunction "P9.3/ESICH3/ESITEST3/A11/C11_55") (pintype "bidirectional"))
    )
    (net (code "97") (name "unconnected-(IC1-P9.4{slash}ESICI0{slash}A12{slash}C12-Pad56)") (class "Default")
      (node (ref "IC1") (pin "56") (pinfunction "P9.4/ESICI0/A12/C12_56") (pintype "bidirectional"))
    )
    (net (code "98") (name "unconnected-(IC1-P9.5{slash}ESICI1{slash}A13{slash}C13-Pad57)") (class "Default")
      (node (ref "IC1") (pin "57") (pinfunction "P9.5/ESICI1/A13/C13_57") (pintype "bidirectional"))
    )
    (net (code "99") (name "unconnected-(IC1-P9.6{slash}ESICI2{slash}A14{slash}C14-Pad58)") (class "Default")
      (node (ref "IC1") (pin "58") (pinfunction "P9.6/ESICI2/A14/C14_58") (pintype "bidirectional"))
    )
    (net (code "100") (name "unconnected-(IC1-P9.7{slash}ESICI3{slash}A15{slash}C15-Pad59)") (class "Default")
      (node (ref "IC1") (pin "59") (pinfunction "P9.7/ESICI3/A15/C15_59") (pintype "bidirectional"))
    )
    (net (code "101") (name "unconnected-(IC1-PJ.0{slash}TDO{slash}TB0OUTH{slash}SMCLK{slash}SRSCG1-Pad25)") (class "Default")
      (node (ref "IC1") (pin "25") (pinfunction "PJ.0/TDO/TB0OUTH/SMCLK/SRSCG1_25") (pintype "bidirectional"))
    )
    (net (code "102") (name "unconnected-(IC1-PJ.1{slash}TDI{slash}TCLK{slash}MCLK{slash}SRSCG0-Pad26)") (class "Default")
      (node (ref "IC1") (pin "26") (pinfunction "PJ.1/TDI/TCLK/MCLK/SRSCG0_26") (pintype "bidirectional"))
    )
    (net (code "103") (name "unconnected-(IC1-PJ.2{slash}TMS{slash}ACLK{slash}SROSCOFF-Pad27)") (class "Default")
      (node (ref "IC1") (pin "27") (pinfunction "PJ.2/TMS/ACLK/SROSCOFF_27") (pintype "bidirectional"))
    )
    (net (code "104") (name "unconnected-(IC1-PJ.3{slash}TCK{slash}COUT{slash}SRCPUOFF-Pad28)") (class "Default")
      (node (ref "IC1") (pin "28") (pinfunction "PJ.3/TCK/COUT/SRCPUOFF_28") (pintype "bidirectional"))
    )
    (net (code "105") (name "unconnected-(IC1-PJ.4{slash}LFXIN-Pad69)") (class "Default")
      (node (ref "IC1") (pin "69") (pinfunction "PJ.4/LFXIN_69") (pintype "bidirectional"))
    )
    (net (code "106") (name "unconnected-(IC1-PJ.5{slash}LFXOUT-Pad70)") (class "Default")
      (node (ref "IC1") (pin "70") (pinfunction "PJ.5/LFXOUT_70") (pintype "bidirectional"))
    )
    (net (code "107") (name "unconnected-(IC1-PJ.6{slash}HFXIN-Pad67)") (class "Default")
      (node (ref "IC1") (pin "67") (pinfunction "PJ.6/HFXIN_67") (pintype "bidirectional"))
    )
    (net (code "108") (name "unconnected-(IC1-PJ.7{slash}HFXOUT-Pad66)") (class "Default")
      (node (ref "IC1") (pin "66") (pinfunction "PJ.7/HFXOUT_66") (pintype "bidirectional"))
    )
    (net (code "109") (name "unconnected-(IC3-CBUS2-Pad13)") (class "Default")
      (node (ref "IC3") (pin "13") (pinfunction "CBUS2_13") (pintype "bidirectional"))
    )
    (net (code "110") (name "unconnected-(IC3-CBUS3-Pad14)") (class "Default")
      (node (ref "IC3") (pin "14") (pinfunction "CBUS3_14") (pintype "bidirectional"))
    )
    (net (code "111") (name "unconnected-(IC3-CBUS4-Pad12)") (class "Default")
      (node (ref "IC3") (pin "12") (pinfunction "CBUS4_12") (pintype "bidirectional"))
    )
    (net (code "112") (name "unconnected-(IC3-OSCI-Pad27)") (class "Default")
      (node (ref "IC3") (pin "27") (pinfunction "OSCI_27") (pintype "input"))
    )
    (net (code "113") (name "unconnected-(IC3-OSCO-Pad28)") (class "Default")
      (node (ref "IC3") (pin "28") (pinfunction "OSCO_28") (pintype "output"))
    )
    (net (code "114") (name "unconnected-(IC3-~{CTS}-Pad11)") (class "Default")
      (node (ref "IC3") (pin "11") (pinfunction "~{CTS}_11") (pintype "input"))
    )
    (net (code "115") (name "unconnected-(IC3-~{DCD}-Pad10)") (class "Default")
      (node (ref "IC3") (pin "10") (pinfunction "~{DCD}_10") (pintype "input"))
    )
    (net (code "116") (name "unconnected-(IC3-~{DSR}-Pad9)") (class "Default")
      (node (ref "IC3") (pin "9") (pinfunction "~{DSR}_9") (pintype "input"))
    )
    (net (code "117") (name "unconnected-(IC3-~{DTR}-Pad2)") (class "Default")
      (node (ref "IC3") (pin "2") (pinfunction "~{DTR}_2") (pintype "output"))
    )
    (net (code "118") (name "unconnected-(IC3-~{RESET}-Pad19)") (class "Default")
      (node (ref "IC3") (pin "19") (pinfunction "~{RESET}_19") (pintype "input"))
    )
    (net (code "119") (name "unconnected-(IC3-~{RI}-Pad6)") (class "Default")
      (node (ref "IC3") (pin "6") (pinfunction "~{RI}_6") (pintype "input"))
    )
    (net (code "120") (name "unconnected-(IC3-~{RTS}-Pad3)") (class "Default")
      (node (ref "IC3") (pin "3") (pinfunction "~{RTS}_3") (pintype "output"))
    )
    (net (code "121") (name "unconnected-(U$2-STAT1-Pad14)") (class "Default")
      (node (ref "U$2") (pin "14") (pinfunction "STAT1_14") (pintype "bidirectional"))
    )
    (net (code "122") (name "unconnected-(U$2-STAT2-Pad11)") (class "Default")
      (node (ref "U$2") (pin "11") (pinfunction "STAT2_11") (pintype "bidirectional"))
    )
    (net (code "123") (name "unconnected-(U$2-WARN1-Pad13)") (class "Default")
      (node (ref "U$2") (pin "13") (pinfunction "WARN1_13") (pintype "bidirectional"))
    )
    (net (code "124") (name "unconnected-(U$2-WARN2-Pad12)") (class "Default")
      (node (ref "U$2") (pin "12") (pinfunction "WARN2_12") (pintype "bidirectional"))
    )
    (net (code "125") (name "unconnected-(U$6-ANT_ON-Pad13)") (class "Default")
      (node (ref "U$6") (pin "13") (pinfunction "ANT_ON_13") (pintype "output"))
    )
    (net (code "126") (name "unconnected-(U$6-SCL-Pad17)") (class "Default")
      (node (ref "U$6") (pin "17") (pinfunction "SCL_17") (pintype "input"))
    )
    (net (code "127") (name "unconnected-(U$6-SDA-Pad16)") (class "Default")
      (node (ref "U$6") (pin "16") (pinfunction "SDA_16") (pintype "bidirectional"))
    )
    (net (code "128") (name "unconnected-(U$6-VCC_RF-Pad14)") (class "Default")
      (node (ref "U$6") (pin "14") (pinfunction "VCC_RF_14") (pintype "output"))
    )
    (net (code "129") (name "unconnected-(U$6-~{RESET}-Pad9)") (class "Default")
      (node (ref "U$6") (pin "9") (pinfunction "~{RESET}_9") (pintype "bidirectional"))
    )
    (net (code "130") (name "unconnected-(X1-ID-Pad4)") (class "Default")
      (node (ref "X1") (pin "4") (pinfunction "ID_4") (pintype "passive"))
    )
  )
)
